# Grove_-_Dry-Reed_Relay_v1_0b.net
KiCad netlist of a schematic drawn in EAGLE
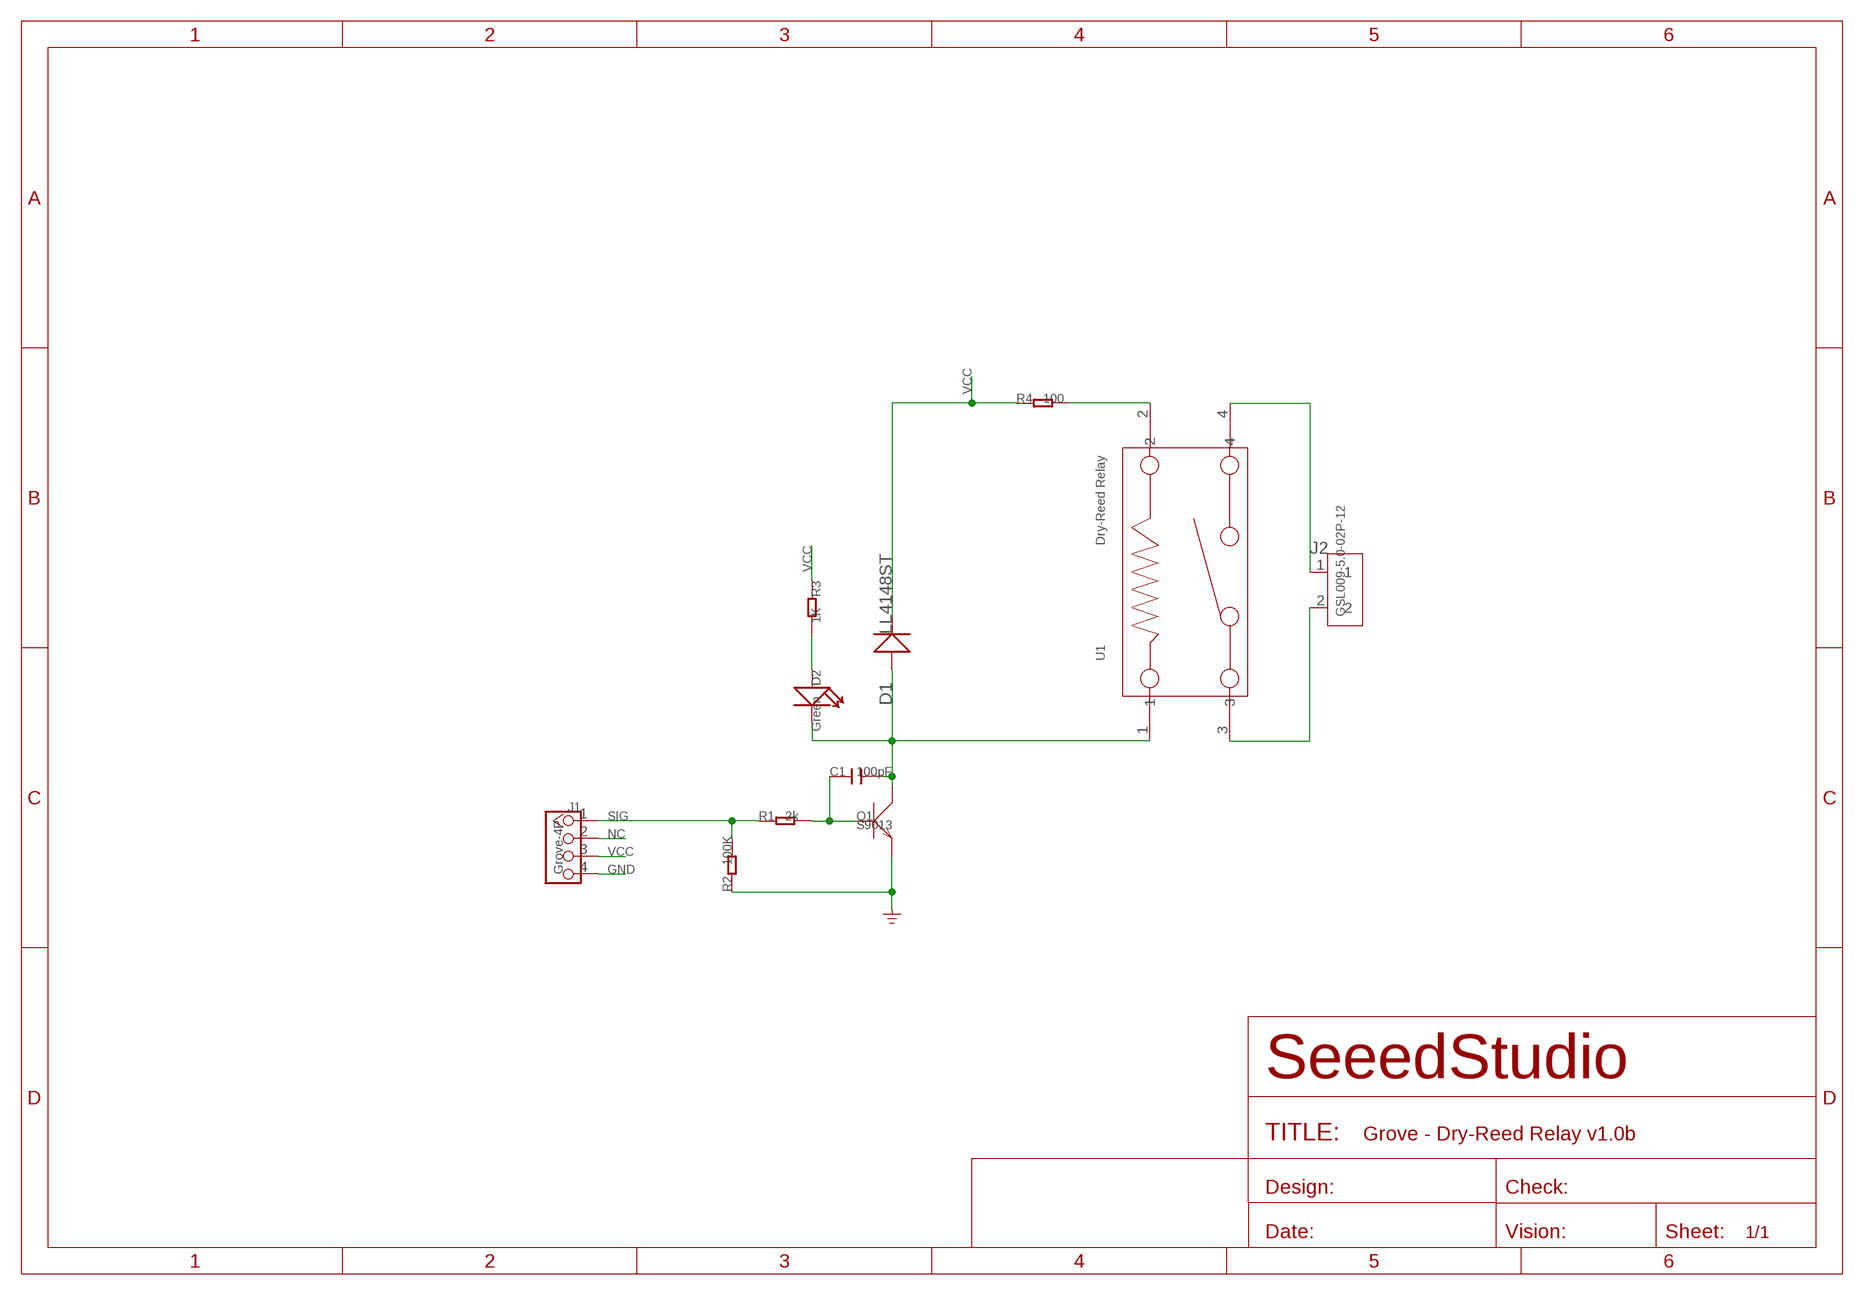
[diagram p0: schematic, sheet 1]

(export (version "E")
  (design (tool "Eeschema 10.0.6"))
  (components
    (comp (ref "C1")
      (value "100pF")
      (footprint "eagle-import:C0603")
      (libsource (lib "eagle-import") (part "C-0603"))
    )
    (comp (ref "D1")
      (value "LL4148ST")
      (footprint "eagle-import:DO-35-SMD")
      (libsource (lib "eagle-import") (part "D'1N4148-SMD'"))
    )
    (comp (ref "D2")
      (value "Green")
      (footprint "eagle-import:LED-0603")
      (libsource (lib "eagle-import") (part "LED'0603'"))
    )
    (comp (ref "J1")
      (value "Grove-4P")
      (footprint "eagle-import:4P-2.0")
      (libsource (lib "eagle-import") (part "TWIG-4P-2.0-2.0"))
    )
    (comp (ref "J2")
      (value "GSL009-5.0-02P-12")
      (footprint "eagle-import:2P-5.08")
      (libsource (lib "eagle-import") (part "SCREW-TERMINAL-2P'5.08'"))
    )
    (comp (ref "Q1")
      (value "S9013")
      (footprint "eagle-import:SOT23")
      (libsource (lib "eagle-import") (part "TRANSISTOR-NPN-SOT23"))
    )
    (comp (ref "R1")
      (value "2k")
      (footprint "eagle-import:R0603")
      (libsource (lib "eagle-import") (part "R-0603"))
    )
    (comp (ref "R2")
      (value "100K")
      (footprint "eagle-import:R0603")
      (libsource (lib "eagle-import") (part "R-0603"))
    )
    (comp (ref "R3")
      (value "1K")
      (footprint "eagle-import:R0603")
      (libsource (lib "eagle-import") (part "R-0603"))
    )
    (comp (ref "R4")
      (value "100")
      (footprint "eagle-import:R0603")
      (libsource (lib "eagle-import") (part "R-0603"))
    )
    (comp (ref "U1")
      (value "Dry-Reed Relay")
      (footprint "eagle-import:4P-25.2X8X9H")
      (libsource (lib "eagle-import") (part "RELAY-BR'BR-500R-H-5VDC'"))
    )
  )
  (nets
    (net (code "1") (name "/NC") (class "Default")
      (node (ref "J1") (pin "2") (pinfunction "2_2") (pintype "bidirectional"))
    )
    (net (code "2") (name "/SIG") (class "Default")
      (node (ref "J1") (pin "1") (pinfunction "1_1") (pintype "bidirectional"))
      (node (ref "R1") (pin "1") (pinfunction "1_1") (pintype "passive"))
      (node (ref "R2") (pin "2") (pinfunction "2_2") (pintype "passive"))
    )
    (net (code "3") (name "/VCC") (class "Default")
      (node (ref "D1") (pin "C") (pinfunction "-_C") (pintype "passive"))
      (node (ref "J1") (pin "3") (pinfunction "3_3") (pintype "bidirectional"))
      (node (ref "R3") (pin "1") (pinfunction "1_1") (pintype "passive"))
      (node (ref "R4") (pin "1") (pinfunction "1_1") (pintype "passive"))
    )
    (net (code "4") (name "GND_POWER") (class "Default")
      (node (ref "J1") (pin "4") (pinfunction "4_4") (pintype "bidirectional"))
      (node (ref "Q1") (pin "2") (pinfunction "E_2") (pintype "passive"))
      (node (ref "R2") (pin "1") (pinfunction "1_1") (pintype "passive"))
    )
    (net (code "5") (name "Net-(D1-+)") (class "Default")
      (node (ref "C1") (pin "2") (pinfunction "2_2") (pintype "passive"))
      (node (ref "D1") (pin "A") (pinfunction "+_A") (pintype "passive"))
      (node (ref "D2") (pin "-") (pinfunction "-_-") (pintype "passive"))
      (node (ref "Q1") (pin "3") (pinfunction "C_3") (pintype "passive"))
      (node (ref "U1") (pin "1") (pinfunction "1_1") (pintype "bidirectional"))
    )
    (net (code "6") (name "Net-(D2-Pad+)") (class "Default")
      (node (ref "D2") (pin "+") (pinfunction "+_+") (pintype "passive"))
      (node (ref "R3") (pin "2") (pinfunction "2_2") (pintype "passive"))
    )
    (net (code "7") (name "Net-(J2-Pad1)") (class "Default")
      (node (ref "J2") (pin "1") (pinfunction "1_1") (pintype "bidirectional"))
      (node (ref "U1") (pin "4") (pinfunction "4_4") (pintype "bidirectional"))
    )
    (net (code "8") (name "Net-(J2-Pad2)") (class "Default")
      (node (ref "J2") (pin "2") (pinfunction "2_2") (pintype "bidirectional"))
      (node (ref "U1") (pin "3") (pinfunction "3_3") (pintype "bidirectional"))
    )
    (net (code "9") (name "Net-(Q1-B)") (class "Default")
      (node (ref "C1") (pin "1") (pinfunction "1_1") (pintype "passive"))
      (node (ref "Q1") (pin "1") (pinfunction "B_1") (pintype "passive"))
      (node (ref "R1") (pin "2") (pinfunction "2_2") (pintype "passive"))
    )
    (net (code "10") (name "Net-(R4-Pad2)") (class "Default")
      (node (ref "R4") (pin "2") (pinfunction "2_2") (pintype "passive"))
      (node (ref "U1") (pin "2") (pinfunction "2_2") (pintype "bidirectional"))
    )
  )
)
